# sc_v1.net
KiCad netlist of a schematic drawn in EAGLE
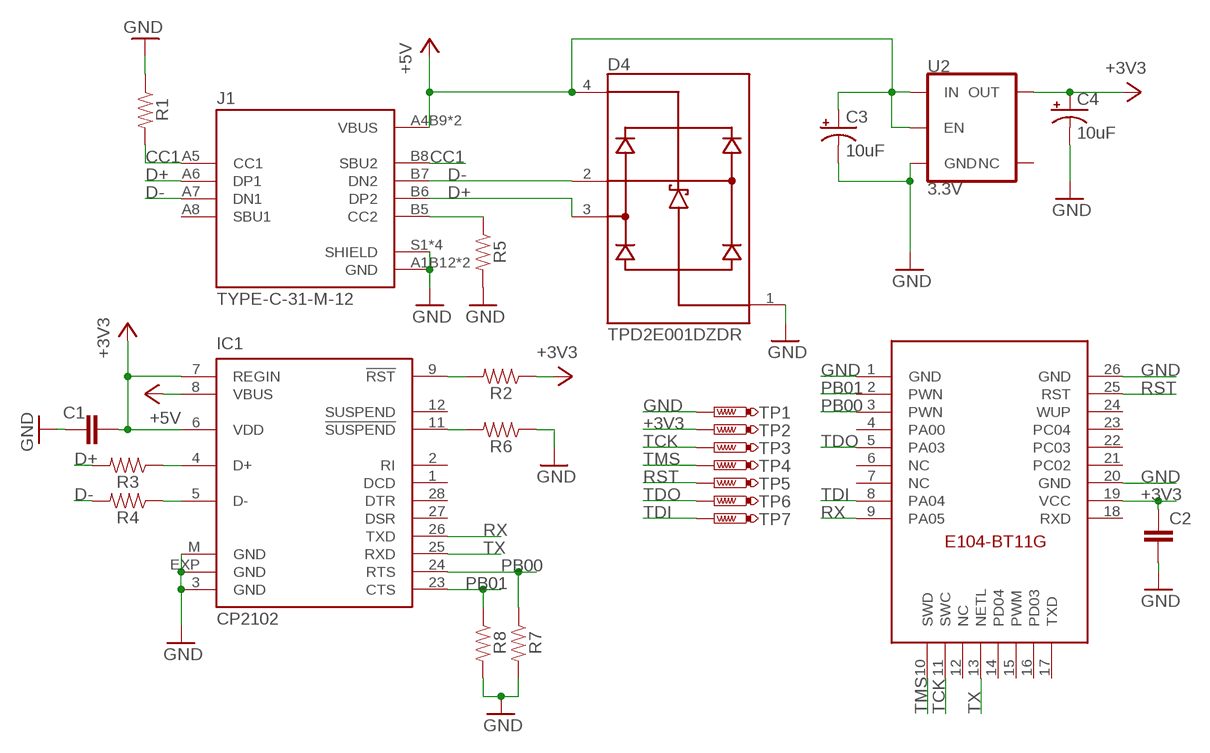
[diagram p0: schematic, sheet 1]

(export (version "E")
  (design (tool "Eeschema 10.0.6"))
  (components
    (comp (ref "C1")
      (value "100nf")
      (footprint "eagle-import:CAPC1005X40N")
      (fields (field (name "MF") "Yageo") (field (name "MP") "RC0402FR-073M6L"))
      (libsource (lib "eagle-import") (part "CAP0402"))
    )
    (comp (ref "C2")
      (value "100n")
      (footprint "eagle-import:CAPC1005X40N")
      (fields (field (name "MF") "Yageo") (field (name "MP") "RC0402FR-073M6L"))
      (libsource (lib "eagle-import") (part "CAP0402"))
    )
    (comp (ref "C3")
      (value "10uF")
      (footprint "eagle-import:0603-POLAR")
      (libsource (lib "eagle-import") (part "10UF-POLAR-0603-6.3V-20%(TANT)"))
    )
    (comp (ref "C4")
      (value "10uF")
      (footprint "eagle-import:0603-POLAR")
      (libsource (lib "eagle-import") (part "10UF-POLAR-0603-6.3V-20%(TANT)"))
    )
    (comp (ref "D4")
      (value "TPD2E001DZDR")
      (footprint "eagle-import:SOT192P237X122-4N")
      (fields (field (name "MF") "Texas Instruments"))
      (libsource (lib "eagle-import") (part "TPD2E001DZDR"))
    )
    (comp (ref "IC1")
      (value "CP2102")
      (footprint "eagle-import:MLP28")
      (fields (field (name "MF") "FARNELL") (field (name "MPN") "CP2102-GM"))
      (libsource (lib "eagle-import") (part "CP2102"))
    )
    (comp (ref "J1")
      (value "TYPE-C-31-M-12")
      (footprint "eagle-import:HRO_TYPE-C-31-M-12")
      (fields (field (name "MF") "HRO Electronics Co., Ltd."))
      (libsource (lib "eagle-import") (part "TYPE-C-31-M-12"))
    )
    (comp (ref "R1")
      (value "5.1k")
      (footprint "eagle-import:0402")
      (libsource (lib "eagle-import") (part "RESISTOR0402"))
    )
    (comp (ref "R2")
      (value "4.7k")
      (footprint "eagle-import:0402")
      (libsource (lib "eagle-import") (part "RESISTOR0402"))
    )
    (comp (ref "R3")
      (value "30Ohm")
      (footprint "eagle-import:0402")
      (libsource (lib "eagle-import") (part "RESISTOR0402"))
    )
    (comp (ref "R4")
      (value "30Ohm")
      (footprint "eagle-import:0402")
      (libsource (lib "eagle-import") (part "RESISTOR0402"))
    )
    (comp (ref "R5")
      (value "5.1k")
      (footprint "eagle-import:0402")
      (libsource (lib "eagle-import") (part "RESISTOR0402"))
    )
    (comp (ref "R6")
      (value "10k")
      (footprint "eagle-import:0402")
      (libsource (lib "eagle-import") (part "RESISTOR0402"))
    )
    (comp (ref "R7")
      (value "10k")
      (footprint "eagle-import:0402")
      (libsource (lib "eagle-import") (part "RESISTOR0402"))
    )
    (comp (ref "R8")
      (value "10k")
      (footprint "eagle-import:0402")
      (libsource (lib "eagle-import") (part "RESISTOR0402"))
    )
    (comp (ref "TP1")
      (value "PTR1TP10R")
      (footprint "eagle-import:TP10R")
      (libsource (lib "eagle-import") (part "PTR1TP10R"))
    )
    (comp (ref "TP2")
      (value "PTR1TP10R")
      (footprint "eagle-import:TP10R")
      (libsource (lib "eagle-import") (part "PTR1TP10R"))
    )
    (comp (ref "TP3")
      (value "PTR1TP10R")
      (footprint "eagle-import:TP10R")
      (libsource (lib "eagle-import") (part "PTR1TP10R"))
    )
    (comp (ref "TP4")
      (value "PTR1TP10R")
      (footprint "eagle-import:TP10R")
      (libsource (lib "eagle-import") (part "PTR1TP10R"))
    )
    (comp (ref "TP5")
      (value "PTR1TP10R")
      (footprint "eagle-import:TP10R")
      (libsource (lib "eagle-import") (part "PTR1TP10R"))
    )
    (comp (ref "TP6")
      (value "PTR1TP10R")
      (footprint "eagle-import:TP10R")
      (libsource (lib "eagle-import") (part "PTR1TP10R"))
    )
    (comp (ref "TP7")
      (value "PTR1TP10R")
      (footprint "eagle-import:TP10R")
      (libsource (lib "eagle-import") (part "PTR1TP10R"))
    )
    (comp (ref "U$1")
      (value "E104-BT11G-PCBPCB")
      (footprint "eagle-import:E104-BT11G-PCB")
      (libsource (lib "eagle-import") (part "E104-BT11G-PCBPCB"))
    )
    (comp (ref "U2")
      (value "3.3V")
      (footprint "eagle-import:SOT23-5")
      (libsource (lib "eagle-import") (part "V_REG_AP2112K-3.3V"))
    )
  )
  (nets
    (net (code "1") (name "+3V3") (class "Default")
      (node (ref "C1") (pin "2") (pinfunction "2_2") (pintype "passive"))
      (node (ref "C2") (pin "1") (pinfunction "1_1") (pintype "passive"))
      (node (ref "C4") (pin "+") (pinfunction "+_+") (pintype "passive"))
      (node (ref "IC1") (pin "6") (pinfunction "VDD_6") (pintype "power_in"))
      (node (ref "IC1") (pin "7") (pinfunction "REGIN_7") (pintype "passive"))
      (node (ref "R2") (pin "1") (pinfunction "1_1") (pintype "passive"))
      (node (ref "TP2") (pin "TP") (pinfunction "TP_TP") (pintype "input"))
      (node (ref "U$1") (pin "19") (pinfunction "VCC_19") (pintype "bidirectional"))
      (node (ref "U2") (pin "5") (pinfunction "OUT_5") (pintype "passive"))
    )
    (net (code "2") (name "+5V") (class "Default")
      (node (ref "C3") (pin "+") (pinfunction "+_+") (pintype "passive"))
      (node (ref "D4") (pin "4") (pinfunction "VCC_4") (pintype "power_in"))
      (node (ref "IC1") (pin "8") (pinfunction "VBUS_8") (pintype "input"))
      (node (ref "J1") (pin "A4B9") (pinfunction "VBUS_A4B9") (pintype "power_in"))
      (node (ref "J1") (pin "B4A9") (pinfunction "VBUS_B4A9") (pintype "power_in"))
      (node (ref "U2") (pin "1") (pinfunction "IN_1") (pintype "input"))
      (node (ref "U2") (pin "3") (pinfunction "EN_3") (pintype "input"))
    )
    (net (code "3") (name "/CC1") (class "Default")
      (node (ref "J1") (pin "A5") (pinfunction "CC1_A5") (pintype "bidirectional"))
      (node (ref "J1") (pin "B8") (pinfunction "SBU2_B8") (pintype "bidirectional"))
      (node (ref "R1") (pin "2") (pinfunction "2_2") (pintype "passive"))
    )
    (net (code "4") (name "/D+") (class "Default")
      (node (ref "D4") (pin "3") (pinfunction "IO2_3") (pintype "bidirectional"))
      (node (ref "J1") (pin "A6") (pinfunction "DP1_A6") (pintype "bidirectional"))
      (node (ref "J1") (pin "B6") (pinfunction "DP2_B6") (pintype "bidirectional"))
      (node (ref "R3") (pin "2") (pinfunction "2_2") (pintype "passive"))
    )
    (net (code "5") (name "/D-") (class "Default")
      (node (ref "D4") (pin "2") (pinfunction "IO1_2") (pintype "bidirectional"))
      (node (ref "J1") (pin "A7") (pinfunction "DN1_A7") (pintype "bidirectional"))
      (node (ref "J1") (pin "B7") (pinfunction "DN2_B7") (pintype "bidirectional"))
      (node (ref "R4") (pin "2") (pinfunction "2_2") (pintype "passive"))
    )
    (net (code "6") (name "/PB00") (class "Default")
      (node (ref "IC1") (pin "24") (pinfunction "RTS_24") (pintype "output"))
      (node (ref "R7") (pin "1") (pinfunction "1_1") (pintype "passive"))
      (node (ref "U$1") (pin "3") (pinfunction "PWN_3") (pintype "bidirectional"))
    )
    (net (code "7") (name "/PB01") (class "Default")
      (node (ref "IC1") (pin "23") (pinfunction "CTS_23") (pintype "input"))
      (node (ref "R8") (pin "1") (pinfunction "1_1") (pintype "passive"))
      (node (ref "U$1") (pin "2") (pinfunction "PWN_2") (pintype "bidirectional"))
    )
    (net (code "8") (name "/RST") (class "Default")
      (node (ref "TP5") (pin "TP") (pinfunction "TP_TP") (pintype "input"))
      (node (ref "U$1") (pin "25") (pinfunction "RST_25") (pintype "bidirectional"))
    )
    (net (code "9") (name "/RX") (class "Default")
      (node (ref "IC1") (pin "26") (pinfunction "TXD_26") (pintype "output"))
      (node (ref "U$1") (pin "9") (pinfunction "PA05_9") (pintype "bidirectional"))
    )
    (net (code "10") (name "/TCK") (class "Default")
      (node (ref "TP3") (pin "TP") (pinfunction "TP_TP") (pintype "input"))
      (node (ref "U$1") (pin "11") (pinfunction "SWC_11") (pintype "bidirectional"))
    )
    (net (code "11") (name "/TDI") (class "Default")
      (node (ref "TP7") (pin "TP") (pinfunction "TP_TP") (pintype "input"))
      (node (ref "U$1") (pin "8") (pinfunction "PA04_8") (pintype "bidirectional"))
    )
    (net (code "12") (name "/TDO") (class "Default")
      (node (ref "TP6") (pin "TP") (pinfunction "TP_TP") (pintype "input"))
      (node (ref "U$1") (pin "5") (pinfunction "PA03_5") (pintype "bidirectional"))
    )
    (net (code "13") (name "/TMS") (class "Default")
      (node (ref "TP4") (pin "TP") (pinfunction "TP_TP") (pintype "input"))
      (node (ref "U$1") (pin "10") (pinfunction "SWD_10") (pintype "bidirectional"))
    )
    (net (code "14") (name "/TX") (class "Default")
      (node (ref "IC1") (pin "25") (pinfunction "RXD_25") (pintype "input"))
      (node (ref "U$1") (pin "13") (pinfunction "NETL_13") (pintype "bidirectional"))
    )
    (net (code "15") (name "GND") (class "Default")
      (node (ref "C1") (pin "1") (pinfunction "1_1") (pintype "passive"))
      (node (ref "C2") (pin "2") (pinfunction "2_2") (pintype "passive"))
      (node (ref "C3") (pin "-") (pinfunction "-_-") (pintype "passive"))
      (node (ref "C4") (pin "-") (pinfunction "-_-") (pintype "passive"))
      (node (ref "D4") (pin "1") (pinfunction "GND_1") (pintype "power_in"))
      (node (ref "IC1") (pin "3") (pinfunction "GND_3") (pintype "power_in"))
      (node (ref "IC1") (pin "EXP") (pinfunction "GND_EXP") (pintype "power_in"))
      (node (ref "IC1") (pin "M") (pinfunction "GND_M") (pintype "power_in"))
      (node (ref "J1") (pin "A1B12") (pinfunction "GND_A1B12") (pintype "power_in"))
      (node (ref "J1") (pin "B1A12") (pinfunction "GND_B1A12") (pintype "power_in"))
      (node (ref "J1") (pin "S1") (pinfunction "SHIELD_S1") (pintype "passive"))
      (node (ref "J1") (pin "S2") (pinfunction "SHIELD_S2") (pintype "passive"))
      (node (ref "J1") (pin "S3") (pinfunction "SHIELD_S3") (pintype "passive"))
      (node (ref "J1") (pin "S4") (pinfunction "SHIELD_S4") (pintype "passive"))
      (node (ref "R1") (pin "1") (pinfunction "1_1") (pintype "passive"))
      (node (ref "R5") (pin "2") (pinfunction "2_2") (pintype "passive"))
      (node (ref "R6") (pin "1") (pinfunction "1_1") (pintype "passive"))
      (node (ref "R7") (pin "2") (pinfunction "2_2") (pintype "passive"))
      (node (ref "R8") (pin "2") (pinfunction "2_2") (pintype "passive"))
      (node (ref "TP1") (pin "TP") (pinfunction "TP_TP") (pintype "input"))
      (node (ref "U$1") (pin "1") (pinfunction "GND_1") (pintype "bidirectional"))
      (node (ref "U$1") (pin "20") (pinfunction "GND_20") (pintype "bidirectional"))
      (node (ref "U$1") (pin "26") (pinfunction "GND_26") (pintype "bidirectional"))
      (node (ref "U2") (pin "2") (pinfunction "GND_2") (pintype "input"))
    )
    (net (code "16") (name "Net-(IC1-D+)") (class "Default")
      (node (ref "IC1") (pin "4") (pinfunction "D+_4") (pintype "bidirectional"))
      (node (ref "R3") (pin "1") (pinfunction "1_1") (pintype "passive"))
    )
    (net (code "17") (name "Net-(IC1-D-)") (class "Default")
      (node (ref "IC1") (pin "5") (pinfunction "D-_5") (pintype "bidirectional"))
      (node (ref "R4") (pin "1") (pinfunction "1_1") (pintype "passive"))
    )
    (net (code "18") (name "Net-(IC1-~{RST})") (class "Default")
      (node (ref "IC1") (pin "9") (pinfunction "~{RST}_9") (pintype "bidirectional"))
      (node (ref "R2") (pin "2") (pinfunction "2_2") (pintype "passive"))
    )
    (net (code "19") (name "Net-(IC1-~{SUSPEND})") (class "Default")
      (node (ref "IC1") (pin "11") (pinfunction "~{SUSPEND}_11") (pintype "output"))
      (node (ref "R6") (pin "2") (pinfunction "2_2") (pintype "passive"))
    )
    (net (code "20") (name "Net-(J1-CC2)") (class "Default")
      (node (ref "J1") (pin "B5") (pinfunction "CC2_B5") (pintype "bidirectional"))
      (node (ref "R5") (pin "1") (pinfunction "1_1") (pintype "passive"))
    )
    (net (code "21") (name "unconnected-(IC1-DCD-Pad1)") (class "Default")
      (node (ref "IC1") (pin "1") (pinfunction "DCD_1") (pintype "input"))
    )
    (net (code "22") (name "unconnected-(IC1-DSR-Pad27)") (class "Default")
      (node (ref "IC1") (pin "27") (pinfunction "DSR_27") (pintype "input"))
    )
    (net (code "23") (name "unconnected-(IC1-DTR-Pad28)") (class "Default")
      (node (ref "IC1") (pin "28") (pinfunction "DTR_28") (pintype "output"))
    )
    (net (code "24") (name "unconnected-(IC1-RI-Pad2)") (class "Default")
      (node (ref "IC1") (pin "2") (pinfunction "RI_2") (pintype "input"))
    )
    (net (code "25") (name "unconnected-(IC1-SUSPEND-Pad12)") (class "Default")
      (node (ref "IC1") (pin "12") (pinfunction "SUSPEND_12") (pintype "output"))
    )
    (net (code "26") (name "unconnected-(J1-SBU1-PadA8)") (class "Default")
      (node (ref "J1") (pin "A8") (pinfunction "SBU1_A8") (pintype "bidirectional"))
    )
    (net (code "27") (name "unconnected-(U$1-NC-Pad6)") (class "Default")
      (node (ref "U$1") (pin "6") (pinfunction "NC_6") (pintype "bidirectional"))
    )
    (net (code "28") (name "unconnected-(U$1-NC-Pad7)") (class "Default")
      (node (ref "U$1") (pin "7") (pinfunction "NC_7") (pintype "bidirectional"))
    )
    (net (code "29") (name "unconnected-(U$1-NC-Pad12)") (class "Default")
      (node (ref "U$1") (pin "12") (pinfunction "NC_12") (pintype "bidirectional"))
    )
    (net (code "30") (name "unconnected-(U$1-PA00-Pad4)") (class "Default")
      (node (ref "U$1") (pin "4") (pinfunction "PA00_4") (pintype "bidirectional"))
    )
    (net (code "31") (name "unconnected-(U$1-PC02-Pad21)") (class "Default")
      (node (ref "U$1") (pin "21") (pinfunction "PC02_21") (pintype "bidirectional"))
    )
    (net (code "32") (name "unconnected-(U$1-PC03-Pad22)") (class "Default")
      (node (ref "U$1") (pin "22") (pinfunction "PC03_22") (pintype "bidirectional"))
    )
    (net (code "33") (name "unconnected-(U$1-PC04-Pad23)") (class "Default")
      (node (ref "U$1") (pin "23") (pinfunction "PC04_23") (pintype "bidirectional"))
    )
    (net (code "34") (name "unconnected-(U$1-PD03-Pad16)") (class "Default")
      (node (ref "U$1") (pin "16") (pinfunction "PD03_16") (pintype "bidirectional"))
    )
    (net (code "35") (name "unconnected-(U$1-PD04-Pad14)") (class "Default")
      (node (ref "U$1") (pin "14") (pinfunction "PD04_14") (pintype "bidirectional"))
    )
    (net (code "36") (name "unconnected-(U$1-PWM-Pad15)") (class "Default")
      (node (ref "U$1") (pin "15") (pinfunction "PWM_15") (pintype "bidirectional"))
    )
    (net (code "37") (name "unconnected-(U$1-RXD-Pad18)") (class "Default")
      (node (ref "U$1") (pin "18") (pinfunction "RXD_18") (pintype "bidirectional"))
    )
    (net (code "38") (name "unconnected-(U$1-TXD-Pad17)") (class "Default")
      (node (ref "U$1") (pin "17") (pinfunction "TXD_17") (pintype "bidirectional"))
    )
    (net (code "39") (name "unconnected-(U$1-WUP-Pad24)") (class "Default")
      (node (ref "U$1") (pin "24") (pinfunction "WUP_24") (pintype "bidirectional"))
    )
    (net (code "40") (name "unconnected-(U2-NC-Pad4)") (class "Default")
      (node (ref "U2") (pin "4") (pinfunction "NC_4") (pintype "no_connect"))
    )
  )
)
